# SCH_PDWD-MINI_R2_2022-02-19.net
KiCad netlist of a schematic drawn in EasyEDA
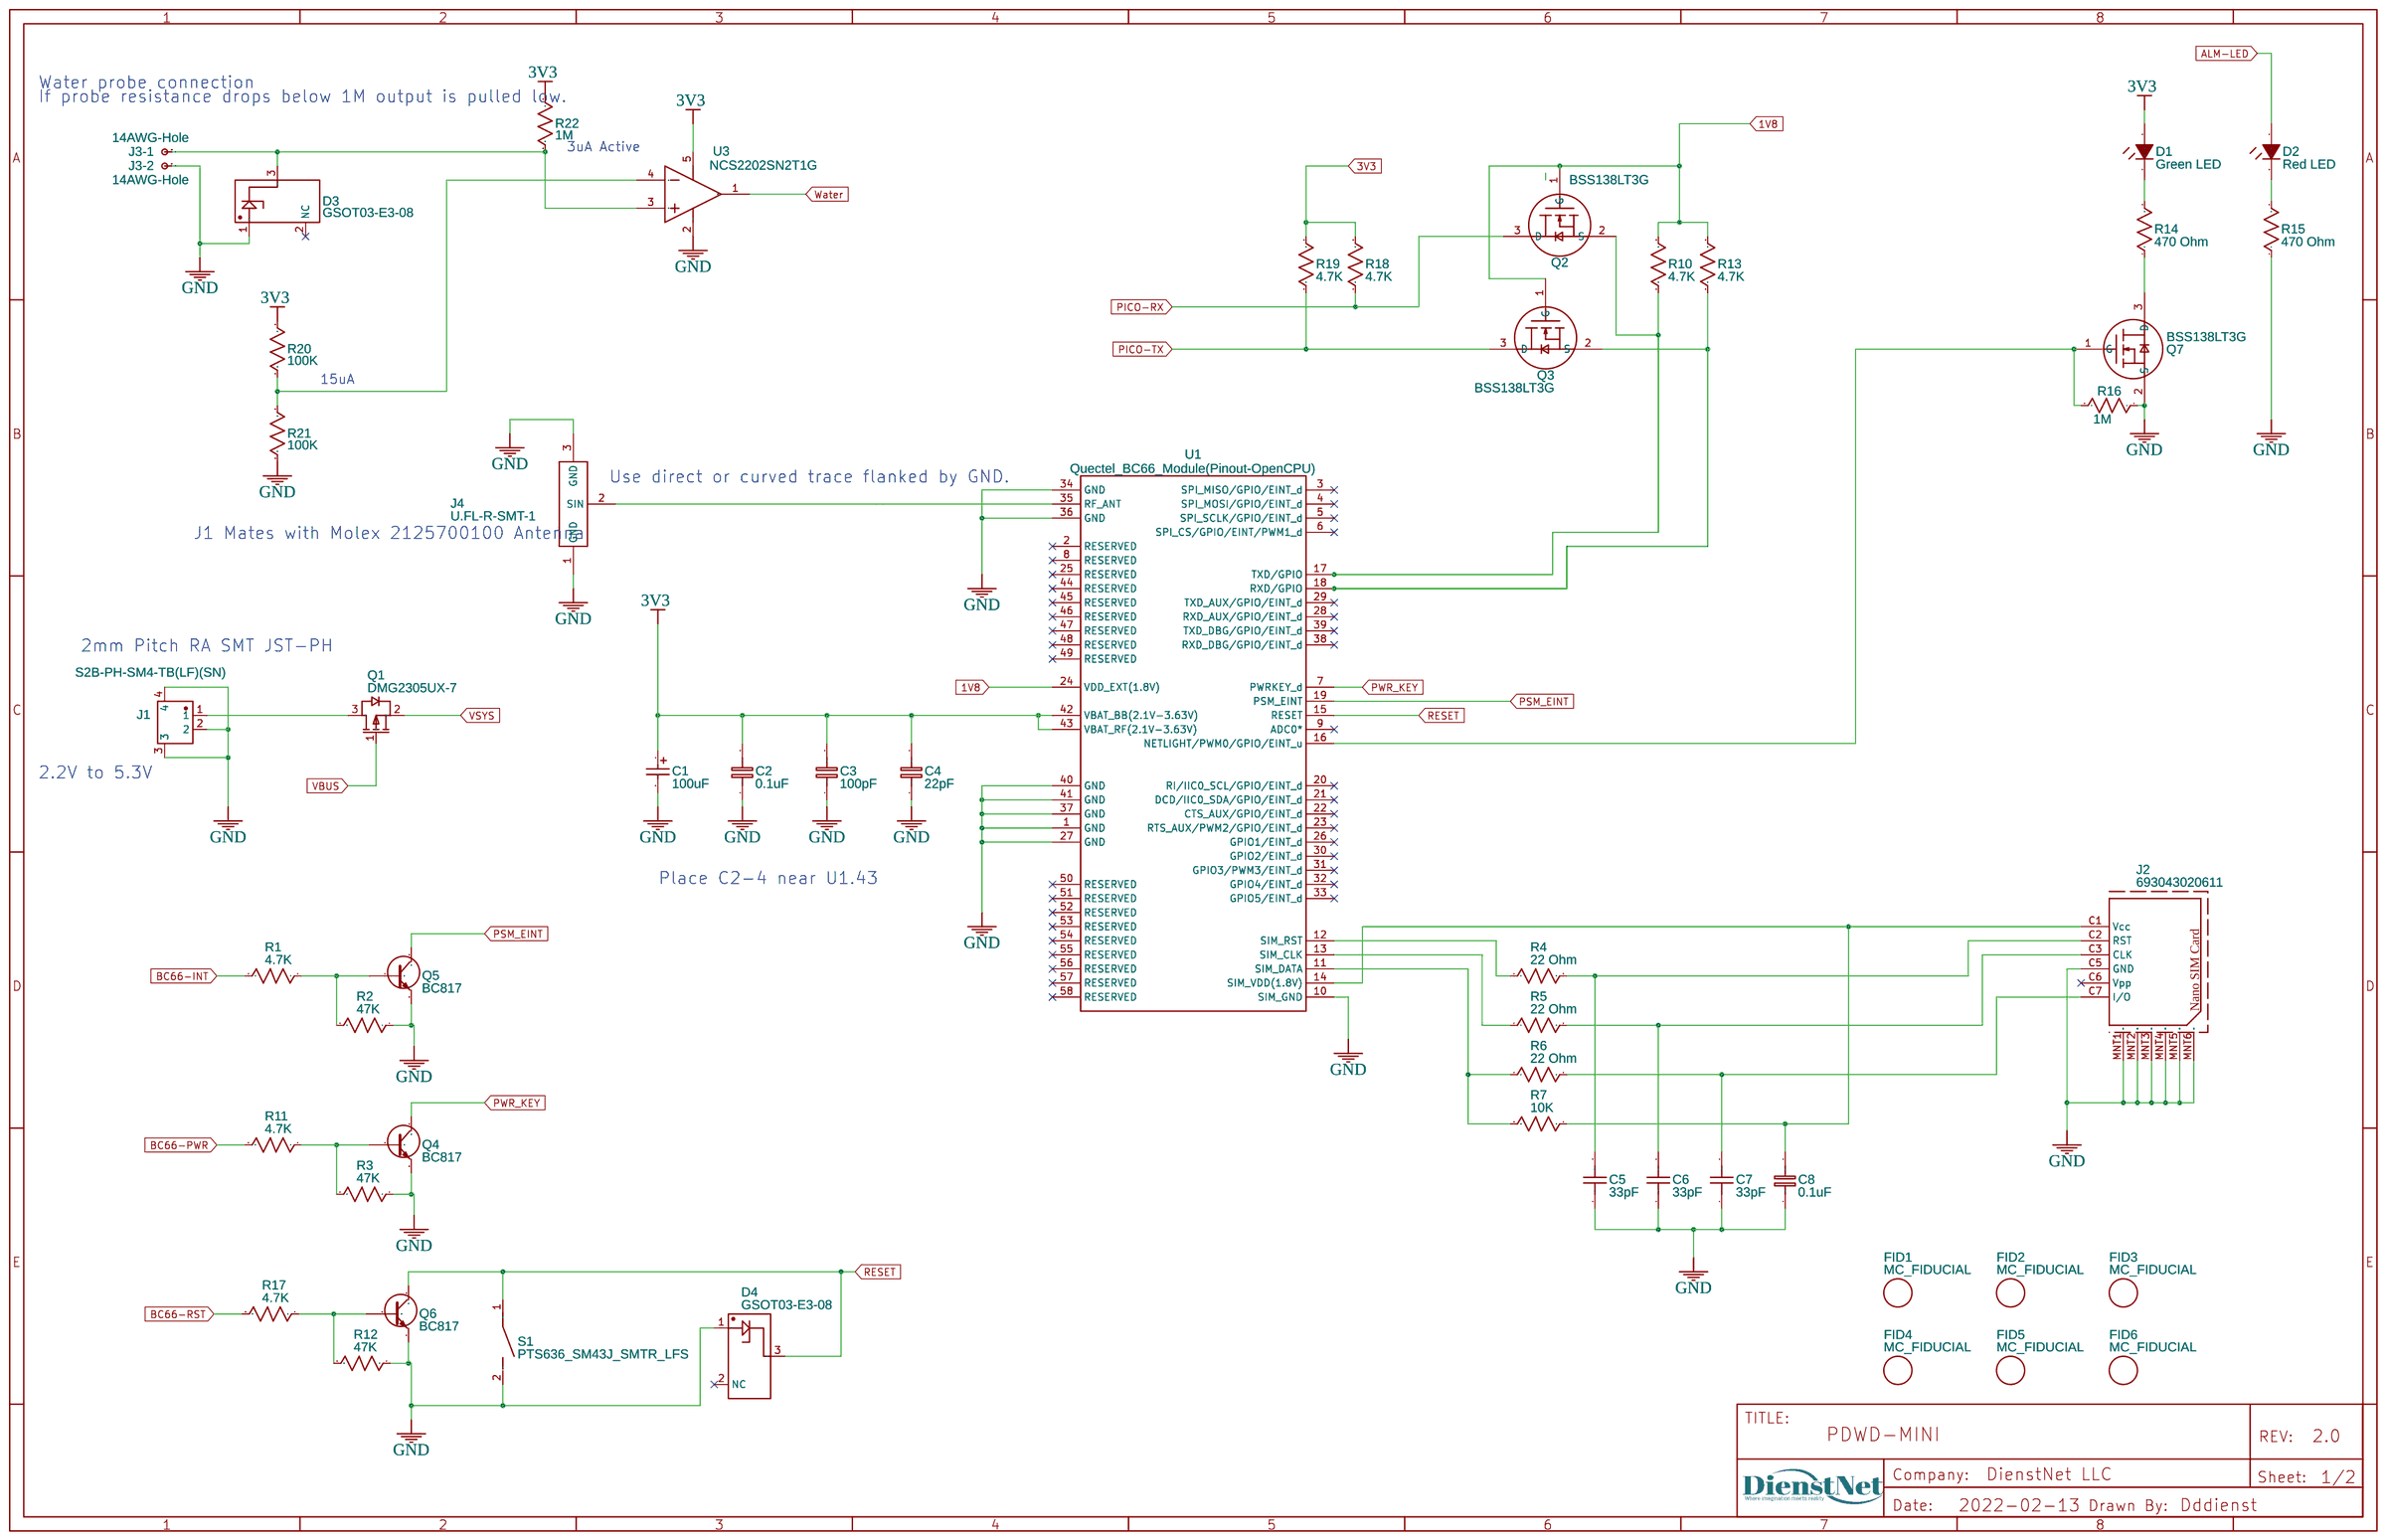
[diagram p0: PDWD-MINI-SCH_Sheet1_R2]
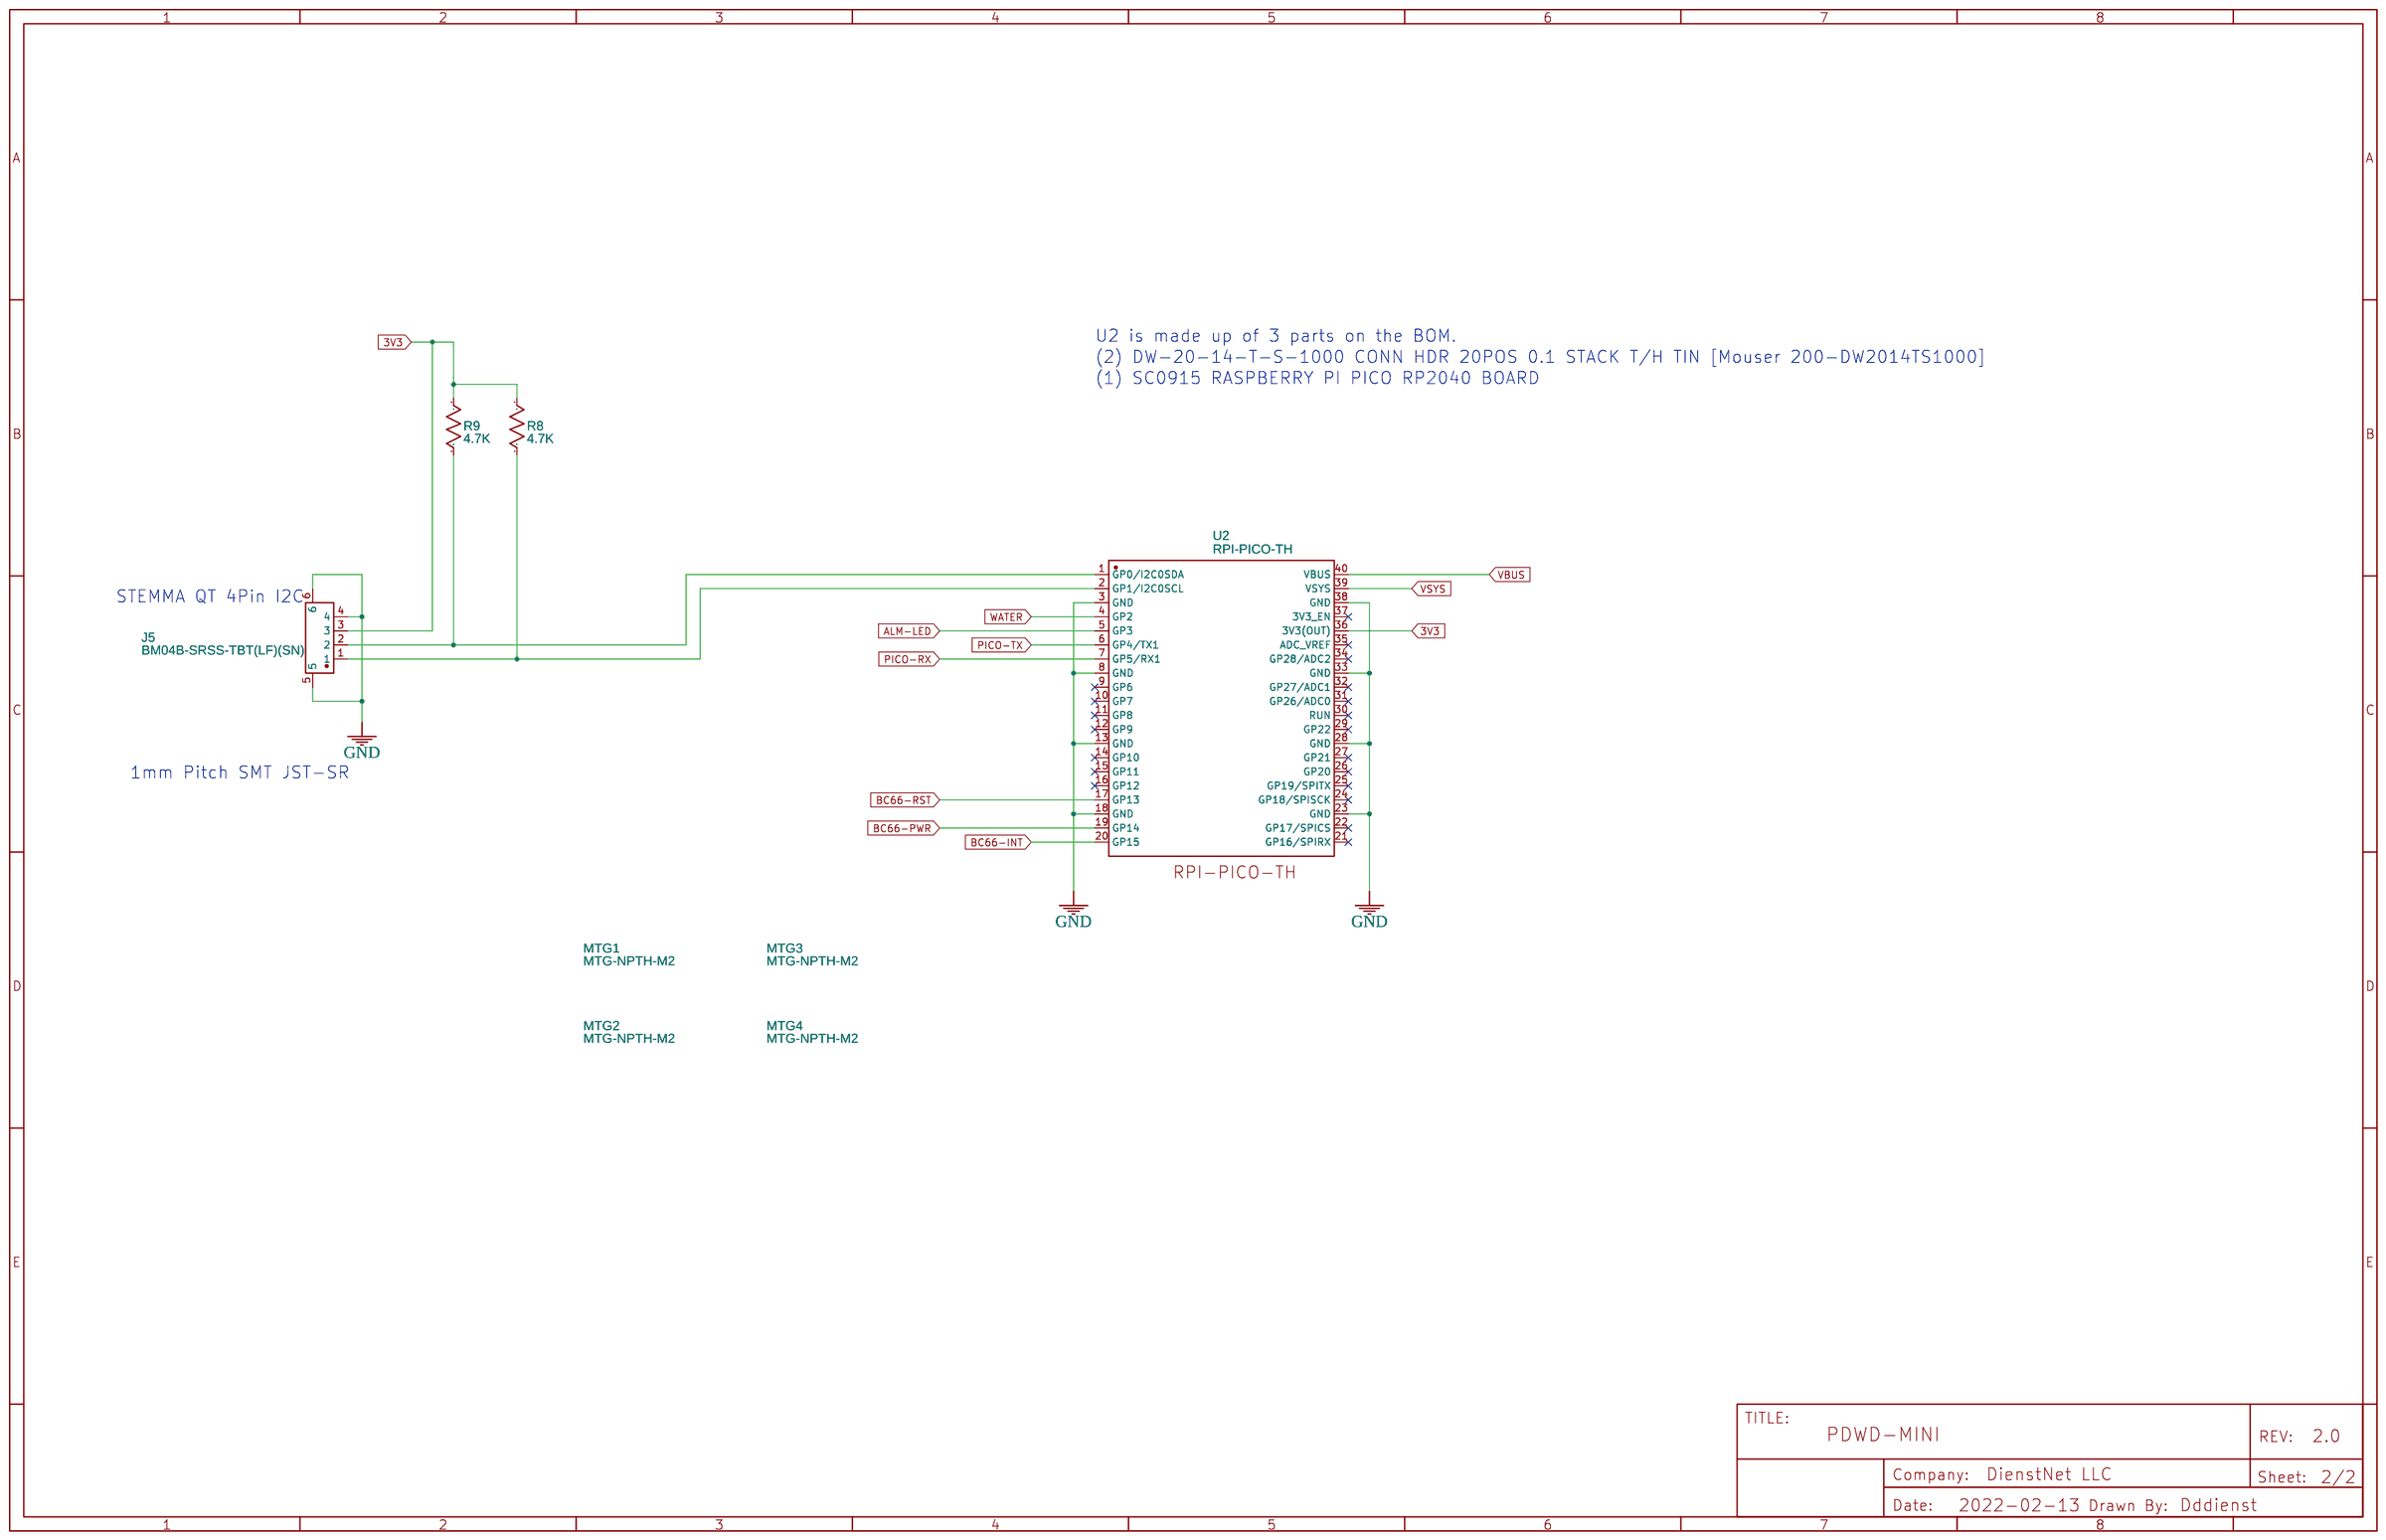
[diagram p1: PICO_Sheet_2_R2]

(export (version "E")
  (design (tool "Eeschema 10.0.6"))
  (components
    (comp (ref "C1")
      (value "100uF")
      (fields
        (field (name "BOM_Manufacturer Part") "TLJA107M006R0500")
        (field (name "BOM_Supplier Part") "C27279")
      )
      (libsource (lib "") (part "TLJA107M006R0800"))
    )
    (comp (ref "C2")
      (value "0.1uF")
      (fields
        (field (name "BOM_Manufacturer Part") "06036C104JAT2A")
        (field (name "BOM_Supplier Part") "C1591")
      )
      (libsource (lib "") (part "C_0603_EU"))
    )
    (comp (ref "C3")
      (value "100pF")
      (fields
        (field (name "BOM_Manufacturer Part") "CC0603KRX7R7BB101")
        (field (name "BOM_Supplier Part") "C62768")
      )
      (libsource (lib "") (part "C_0603_EU"))
    )
    (comp (ref "C4")
      (value "22pF")
      (fields
        (field (name "BOM_Manufacturer Part") "CC0603JRX7R9BB104")
        (field (name "BOM_Supplier Part") "C91183")
      )
      (libsource (lib "") (part "C_0603_EU"))
    )
    (comp (ref "C5")
      (value "33pF")
      (fields
        (field (name "BOM_Manufacturer Part") "C0603C330J5GACTU")
        (field (name "BOM_Supplier Part") "C599724")
      )
      (libsource (lib "") (part "C_0805_US"))
    )
    (comp (ref "C6")
      (value "33pF")
      (fields
        (field (name "BOM_Manufacturer Part") "C0603C330J5GACTU")
        (field (name "BOM_Supplier Part") "C599724")
      )
      (libsource (lib "") (part "C_0805_US"))
    )
    (comp (ref "C7")
      (value "33pF")
      (fields
        (field (name "BOM_Manufacturer Part") "C0603C330J5GACTU")
        (field (name "BOM_Supplier Part") "C599724")
      )
      (libsource (lib "") (part "C_0805_US"))
    )
    (comp (ref "C8")
      (value "0.1uF")
      (fields
        (field (name "BOM_Manufacturer Part") "06036C104JAT2A")
        (field (name "BOM_Supplier Part") "C1591")
      )
      (libsource (lib "") (part "C_0603_EU"))
    )
    (comp (ref "D1")
      (value "Green LED")
      (fields
        (field (name "BOM_Manufacturer Part") "SM0805GCL")
        (field (name "BOM_Supplier Part") "749-SM0805GCL")
      )
      (libsource (lib "") (part "Red LED - SMD"))
    )
    (comp (ref "D2")
      (value "Red LED")
      (fields
        (field (name "BOM_Manufacturer Part") "SM0805HCL")
        (field (name "BOM_Supplier Part") "749-SM0805HCL")
      )
      (libsource (lib "") (part "Red LED - SMD"))
    )
    (comp (ref "D3") (value "GSOT03-E3-08") (libsource (lib "") (part "GSOT03-E3-08_1")))
    (comp (ref "D4") (value "GSOT03-E3-08") (libsource (lib "") (part "GSOT03-E3-08")))
    (comp (ref "FID1") (value "MC_FIDUCIAL") (libsource (lib "") (part "MC_FIDUCIAL")))
    (comp (ref "FID2") (value "MC_FIDUCIAL") (libsource (lib "") (part "MC_FIDUCIAL")))
    (comp (ref "FID3") (value "MC_FIDUCIAL") (libsource (lib "") (part "MC_FIDUCIAL")))
    (comp (ref "FID4") (value "MC_FIDUCIAL") (libsource (lib "") (part "MC_FIDUCIAL")))
    (comp (ref "FID5") (value "MC_FIDUCIAL") (libsource (lib "") (part "MC_FIDUCIAL")))
    (comp (ref "FID6") (value "MC_FIDUCIAL") (libsource (lib "") (part "MC_FIDUCIAL")))
    (comp (ref "J1")
      (value "S2B-PH-SM4-TB(LF)(SN)")
      (fields (field (name "BOM_Supplier Part") "C295747"))
      (libsource (lib "") (part "S2B-PH-SM4-TB(LF)(SN)"))
    )
    (comp (ref "J2")
      (value "693043020611")
      (fields (field (name "BOM_Supplier Part") "732-5954-1-ND"))
      (libsource (lib "") (part "693043020611"))
    )
    (comp (ref "J3-1") (value "14AWG-Hole") (libsource (lib "") (part "14AWG-Hole")))
    (comp (ref "J3-2") (value "14AWG-Hole") (libsource (lib "") (part "14AWG-Hole")))
    (comp (ref "J4")
      (value "U.FL-R-SMT-1")
      (fields
        (field (name "BOM_Manufacturer Part") "U.FL-R-SMT-1(80)")
        (field (name "BOM_Supplier Part") "C88374")
      )
      (libsource (lib "") (part "U.FL-R-SMT-1(80)"))
    )
    (comp (ref "Q1")
      (value "DMG2305UX-7")
      (fields (field (name "BOM_Supplier Part") "C150470"))
      (libsource (lib "") (part "DMG2305UX-7"))
    )
    (comp (ref "Q2")
      (value "BSS138LT3G")
      (fields (field (name "BOM_Supplier Part") "C83790"))
      (libsource (lib "") (part "BSS138LT3G"))
    )
    (comp (ref "Q3")
      (value "BSS138LT3G")
      (fields (field (name "BOM_Supplier Part") "C83790"))
      (libsource (lib "") (part "BSS138LT3G"))
    )
    (comp (ref "Q4")
      (value "BC817")
      (fields
        (field (name "BOM_Manufacturer Part") "BC817-16LT1G")
        (field (name "BOM_Supplier Part") "C94373")
      )
      (libsource (lib "") (part "BC817_1"))
    )
    (comp (ref "Q5")
      (value "BC817")
      (fields
        (field (name "BOM_Manufacturer Part") "BC817-16LT1G")
        (field (name "BOM_Supplier Part") "C94373")
      )
      (libsource (lib "") (part "BC817_2"))
    )
    (comp (ref "Q6")
      (value "BC817")
      (fields
        (field (name "BOM_Manufacturer Part") "BC817-16LT1G")
        (field (name "BOM_Supplier Part") "C94373")
      )
      (libsource (lib "") (part "BC817"))
    )
    (comp (ref "Q7")
      (value "BSS138LT3G")
      (fields (field (name "BOM_Supplier Part") "C83790"))
      (libsource (lib "") (part "BSS138LT3G_1"))
    )
    (comp (ref "R1")
      (value "4.7K")
      (fields
        (field (name "BOM_Manufacturer Part") "ERJ-3GEYJ472V")
        (field (name "BOM_Supplier Part") "C278641")
      )
      (libsource (lib "") (part "R_0805_US"))
    )
    (comp (ref "R2")
      (value "47K")
      (fields
        (field (name "BOM_Manufacturer Part") "ERJ-3GEYJ473V")
        (field (name "BOM_Supplier Part") "C427281")
      )
      (libsource (lib "") (part "R_0805_US"))
    )
    (comp (ref "R3")
      (value "47K")
      (fields
        (field (name "BOM_Manufacturer Part") "ERJ-3GEYJ473V")
        (field (name "BOM_Supplier Part") "C427281")
      )
      (libsource (lib "") (part "R_0805_US"))
    )
    (comp (ref "R4")
      (value "22 Ohm")
      (fields
        (field (name "BOM_Manufacturer Part") "ERJ-3GEYJ220V")
        (field (name "BOM_Supplier Part") "C278638")
      )
      (libsource (lib "") (part "R_0805_US_2"))
    )
    (comp (ref "R5")
      (value "22 Ohm")
      (fields
        (field (name "BOM_Manufacturer Part") "ERJ-3GEYJ220V")
        (field (name "BOM_Supplier Part") "C278638")
      )
      (libsource (lib "") (part "R_0805_US_2"))
    )
    (comp (ref "R6")
      (value "22 Ohm")
      (fields
        (field (name "BOM_Manufacturer Part") "ERJ-3GEYJ220V")
        (field (name "BOM_Supplier Part") "C278638")
      )
      (libsource (lib "") (part "R_0805_US_2"))
    )
    (comp (ref "R7")
      (value "10K")
      (fields
        (field (name "BOM_Manufacturer Part") "ERJ-3GEYJ103V")
        (field (name "BOM_Supplier Part") "C169849")
      )
      (libsource (lib "") (part "R_0805_US"))
    )
    (comp (ref "R10")
      (value "4.7K")
      (fields
        (field (name "BOM_Manufacturer Part") "ERJ-3GEYJ472V")
        (field (name "BOM_Supplier Part") "C278641")
      )
      (libsource (lib "") (part "R_0805_US_1"))
    )
    (comp (ref "R11")
      (value "4.7K")
      (fields
        (field (name "BOM_Manufacturer Part") "ERJ-3GEYJ472V")
        (field (name "BOM_Supplier Part") "C278641")
      )
      (libsource (lib "") (part "R_0805_US"))
    )
    (comp (ref "R12")
      (value "47K")
      (fields
        (field (name "BOM_Manufacturer Part") "ERJ-3GEYJ473V")
        (field (name "BOM_Supplier Part") "C427281")
      )
      (libsource (lib "") (part "R_0805_US"))
    )
    (comp (ref "R13")
      (value "4.7K")
      (fields
        (field (name "BOM_Manufacturer Part") "ERJ-3GEYJ472V")
        (field (name "BOM_Supplier Part") "C278641")
      )
      (libsource (lib "") (part "R_0805_US_1"))
    )
    (comp (ref "R14")
      (value "470 Ohm")
      (fields
        (field (name "BOM_Manufacturer Part") "ERJ-3GEYJ471V")
        (field (name "BOM_Supplier Part") "C169852")
      )
      (libsource (lib "") (part "R_0805_US_1"))
    )
    (comp (ref "R15")
      (value "470 Ohm")
      (fields
        (field (name "BOM_Manufacturer Part") "ERJ-3GEYJ471V")
        (field (name "BOM_Supplier Part") "C169852")
      )
      (libsource (lib "") (part "R_0805_US_1"))
    )
    (comp (ref "R16")
      (value "1M")
      (fields
        (field (name "BOM_Manufacturer Part") "ERJ-3GEYJ105V")
        (field (name "BOM_Supplier Part") "C278634")
      )
      (libsource (lib "") (part "R_0805_US"))
    )
    (comp (ref "R17")
      (value "4.7K")
      (fields
        (field (name "BOM_Manufacturer Part") "ERJ-3GEYJ472V")
        (field (name "BOM_Supplier Part") "C278641")
      )
      (libsource (lib "") (part "R_0805_US"))
    )
    (comp (ref "R18")
      (value "4.7K")
      (fields
        (field (name "BOM_Manufacturer Part") "ERJ-3GEYJ472V")
        (field (name "BOM_Supplier Part") "C278641")
      )
      (libsource (lib "") (part "R_0805_US_1"))
    )
    (comp (ref "R19")
      (value "4.7K")
      (fields
        (field (name "BOM_Manufacturer Part") "ERJ-3GEYJ472V")
        (field (name "BOM_Supplier Part") "C278641")
      )
      (libsource (lib "") (part "R_0805_US_1"))
    )
    (comp (ref "R20")
      (value "100K")
      (fields
        (field (name "BOM_Manufacturer Part") "ERJ-3GEYJ104V")
        (field (name "BOM_Supplier Part") "C427284")
      )
      (libsource (lib "") (part "R_0805_US_3"))
    )
    (comp (ref "R21")
      (value "100K")
      (fields
        (field (name "BOM_Manufacturer Part") "ERJ-3GEYJ104V")
        (field (name "BOM_Supplier Part") "C427284")
      )
      (libsource (lib "") (part "R_0805_US_3"))
    )
    (comp (ref "R22")
      (value "1M")
      (fields
        (field (name "BOM_Manufacturer Part") "ERJ-3GEYJ105V")
        (field (name "BOM_Supplier Part") "C278634")
      )
      (libsource (lib "") (part "R_0805_US_3"))
    )
    (comp (ref "S1")
      (value "PTS636_SM43J_SMTR_LFS")
      (fields
        (field (name "BOM_Manufacturer Part") "PTS636 SM43J SMTR LFS")
        (field (name "BOM_Supplier Part") "611-PTS636SM43JSMTRL")
      )
      (libsource (lib "") (part "PTS636_SM43J_SMTR_LFS"))
    )
    (comp (ref "U1")
      (value "Quectel_BC66_Module(Pinout-OpenCPU)")
      (fields
        (field (name "BOM_Manufacturer Part") "BC66NB-04-STD")
        (field (name "BOM_Supplier Part") "277-BC66NB-04-STD")
      )
      (libsource (lib "") (part "Quectel_BC66_Module(Pinout-OpenCPU)"))
    )
    (comp (ref "U3")
      (value "NCS2202SN2T1G")
      (fields (field (name "BOM_Supplier Part") "C94396"))
      (libsource (lib "") (part "NCS2202SN2T1G"))
    )
    (comp (ref "J5")
      (value "BM04B-SRSS-TBT(LF)(SN)")
      (fields (field (name "BOM_Supplier Part") "C495539"))
      (libsource (lib "") (part "BM04B-SRSS-TBT(LF)(SN)"))
    )
    (comp (ref "MTG1") (value "MTG-NPTH-M2") (libsource (lib "") (part "MTG-NPTH-M2")))
    (comp (ref "MTG2") (value "MTG-NPTH-M2") (libsource (lib "") (part "MTG-NPTH-M2")))
    (comp (ref "MTG3") (value "MTG-NPTH-M2") (libsource (lib "") (part "MTG-NPTH-M2")))
    (comp (ref "MTG4") (value "MTG-NPTH-M2") (libsource (lib "") (part "MTG-NPTH-M2")))
    (comp (ref "R8")
      (value "4.7K")
      (fields
        (field (name "BOM_Manufacturer Part") "ERJ-3GEYJ472V")
        (field (name "BOM_Supplier Part") "C278641")
      )
      (libsource (lib "") (part "R_0805_US"))
    )
    (comp (ref "R9")
      (value "4.7K")
      (fields
        (field (name "BOM_Manufacturer Part") "ERJ-3GEYJ472V")
        (field (name "BOM_Supplier Part") "C278641")
      )
      (libsource (lib "") (part "R_0805_US"))
    )
    (comp (ref "U2")
      (value "RPI-PICO-TH")
      (fields
        (field (name "BOM_Manufacturer Part") "SC0915")
        (field (name "BOM_Supplier Part") "2648-SC0915CT-ND")
      )
      (libsource (lib "") (part "RPI-PICO-TH"))
    )
  )
  (nets
    (net (code "1") (name "1V8") (class "Default")
      (node (ref "Q2") (pin "1") (pinfunction "G_1") (pintype "unspecified"))
      (node (ref "Q3") (pin "1") (pinfunction "G_1") (pintype "unspecified"))
      (node (ref "R10") (pin "2") (pinfunction "2_2") (pintype "unspecified"))
      (node (ref "R13") (pin "2") (pinfunction "2_2") (pintype "unspecified"))
      (node (ref "U1") (pin "24") (pinfunction "VDD_EXT(1.8V)_24") (pintype "unspecified"))
    )
    (net (code "2") (name "3V3") (class "Default")
      (node (ref "C1") (pin "1") (pinfunction "1_1") (pintype "input"))
      (node (ref "C2") (pin "2") (pinfunction "2_2") (pintype "unspecified"))
      (node (ref "C3") (pin "2") (pinfunction "2_2") (pintype "unspecified"))
      (node (ref "C4") (pin "2") (pinfunction "2_2") (pintype "unspecified"))
      (node (ref "D1") (pin "1") (pinfunction "A_1") (pintype "unspecified"))
      (node (ref "J5") (pin "3") (pinfunction "3_3") (pintype "unspecified"))
      (node (ref "R18") (pin "2") (pinfunction "2_2") (pintype "unspecified"))
      (node (ref "R19") (pin "2") (pinfunction "2_2") (pintype "unspecified"))
      (node (ref "R20") (pin "1") (pinfunction "1_1") (pintype "unspecified"))
      (node (ref "R22") (pin "1") (pinfunction "1_1") (pintype "unspecified"))
      (node (ref "R8") (pin "2") (pinfunction "2_2") (pintype "unspecified"))
      (node (ref "R9") (pin "2") (pinfunction "2_2") (pintype "unspecified"))
      (node (ref "U1") (pin "42") (pinfunction "VBAT_BB(2.1V-3.63V)_42") (pintype "unspecified"))
      (node (ref "U1") (pin "43") (pinfunction "VBAT_RF(2.1V-3.63V)_43") (pintype "unspecified"))
      (node (ref "U2") (pin "36") (pinfunction "3V3(OUT)_36") (pintype "unspecified"))
      (node (ref "U3") (pin "5") (pinfunction "+V_5") (pintype "passive"))
    )
    (net (code "3") (name "ALM-LED") (class "Default")
      (node (ref "D2") (pin "1") (pinfunction "A_1") (pintype "unspecified"))
      (node (ref "U2") (pin "5") (pinfunction "GP3_5") (pintype "unspecified"))
    )
    (net (code "4") (name "BC66-INT") (class "Default")
      (node (ref "R1") (pin "2") (pinfunction "2_2") (pintype "unspecified"))
      (node (ref "U2") (pin "20") (pinfunction "GP15_20") (pintype "unspecified"))
    )
    (net (code "5") (name "BC66-PWR") (class "Default")
      (node (ref "R11") (pin "2") (pinfunction "2_2") (pintype "unspecified"))
      (node (ref "U2") (pin "19") (pinfunction "GP14_19") (pintype "unspecified"))
    )
    (net (code "6") (name "BC66-RST") (class "Default")
      (node (ref "R17") (pin "2") (pinfunction "2_2") (pintype "unspecified"))
      (node (ref "U2") (pin "17") (pinfunction "GP13_17") (pintype "unspecified"))
    )
    (net (code "7") (name "GND") (class "Default")
      (node (ref "C1") (pin "2") (pinfunction "2_2") (pintype "input"))
      (node (ref "C2") (pin "1") (pinfunction "1_1") (pintype "unspecified"))
      (node (ref "C3") (pin "1") (pinfunction "1_1") (pintype "unspecified"))
      (node (ref "C4") (pin "1") (pinfunction "1_1") (pintype "unspecified"))
      (node (ref "C5") (pin "1") (pinfunction "1_1") (pintype "unspecified"))
      (node (ref "C6") (pin "1") (pinfunction "1_1") (pintype "unspecified"))
      (node (ref "C7") (pin "1") (pinfunction "1_1") (pintype "unspecified"))
      (node (ref "C8") (pin "1") (pinfunction "1_1") (pintype "unspecified"))
      (node (ref "D3") (pin "1") (pinfunction "IN_1") (pintype "unspecified"))
      (node (ref "D4") (pin "1") (pinfunction "IN_1") (pintype "unspecified"))
      (node (ref "J1") (pin "2") (pinfunction "2_2") (pintype "unspecified"))
      (node (ref "J1") (pin "3") (pinfunction "3_3") (pintype "unspecified"))
      (node (ref "J1") (pin "4") (pinfunction "4_4") (pintype "unspecified"))
      (node (ref "J2") (pin "C5") (pinfunction "GND_C5") (pintype "unspecified"))
      (node (ref "J2") (pin "MNT1") (pinfunction "Shield_MNT1") (pintype "unspecified"))
      (node (ref "J2") (pin "MNT2") (pinfunction "Shield_MNT2") (pintype "unspecified"))
      (node (ref "J2") (pin "MNT3") (pinfunction "Shield_MNT3") (pintype "unspecified"))
      (node (ref "J2") (pin "MNT4") (pinfunction "Shield_MNT4") (pintype "unspecified"))
      (node (ref "J2") (pin "MNT5") (pinfunction "Shield_MNT5") (pintype "unspecified"))
      (node (ref "J2") (pin "MNT6") (pinfunction "Shield_MNT6") (pintype "unspecified"))
      (node (ref "J3-2") (pin "P$1") (pinfunction "P$1_P$1") (pintype "unspecified"))
      (node (ref "J4") (pin "1") (pinfunction "GND_1") (pintype "unspecified"))
      (node (ref "J4") (pin "3") (pinfunction "GND_3") (pintype "unspecified"))
      (node (ref "J5") (pin "4") (pinfunction "4_4") (pintype "unspecified"))
      (node (ref "J5") (pin "5") (pinfunction "5_5") (pintype "unspecified"))
      (node (ref "J5") (pin "6") (pinfunction "6_6") (pintype "unspecified"))
      (node (ref "Q4") (pin "2") (pinfunction "E_2") (pintype "unspecified"))
      (node (ref "Q5") (pin "2") (pinfunction "E_2") (pintype "unspecified"))
      (node (ref "Q6") (pin "2") (pinfunction "E_2") (pintype "unspecified"))
      (node (ref "Q7") (pin "2") (pinfunction "S_2") (pintype "unspecified"))
      (node (ref "R12") (pin "1") (pinfunction "1_1") (pintype "unspecified"))
      (node (ref "R15") (pin "1") (pinfunction "1_1") (pintype "unspecified"))
      (node (ref "R16") (pin "1") (pinfunction "1_1") (pintype "unspecified"))
      (node (ref "R2") (pin "1") (pinfunction "1_1") (pintype "unspecified"))
      (node (ref "R21") (pin "2") (pinfunction "2_2") (pintype "unspecified"))
      (node (ref "R3") (pin "1") (pinfunction "1_1") (pintype "unspecified"))
      (node (ref "S1") (pin "2") (pinfunction "NO_2") (pintype "bidirectional"))
      (node (ref "U1") (pin "1") (pinfunction "GND_1") (pintype "unspecified"))
      (node (ref "U1") (pin "10") (pinfunction "SIM_GND_10") (pintype "unspecified"))
      (node (ref "U1") (pin "27") (pinfunction "GND_27") (pintype "unspecified"))
      (node (ref "U1") (pin "34") (pinfunction "GND_34") (pintype "unspecified"))
      (node (ref "U1") (pin "36") (pinfunction "GND_36") (pintype "unspecified"))
      (node (ref "U1") (pin "37") (pinfunction "GND_37") (pintype "unspecified"))
      (node (ref "U1") (pin "40") (pinfunction "GND_40") (pintype "unspecified"))
      (node (ref "U1") (pin "41") (pinfunction "GND_41") (pintype "unspecified"))
      (node (ref "U2") (pin "13") (pinfunction "GND_13") (pintype "unspecified"))
      (node (ref "U2") (pin "18") (pinfunction "GND_18") (pintype "unspecified"))
      (node (ref "U2") (pin "23") (pinfunction "GND_23") (pintype "unspecified"))
      (node (ref "U2") (pin "28") (pinfunction "GND_28") (pintype "unspecified"))
      (node (ref "U2") (pin "3") (pinfunction "GND_3") (pintype "unspecified"))
      (node (ref "U2") (pin "33") (pinfunction "GND_33") (pintype "unspecified"))
      (node (ref "U2") (pin "38") (pinfunction "GND_38") (pintype "unspecified"))
      (node (ref "U2") (pin "8") (pinfunction "GND_8") (pintype "unspecified"))
      (node (ref "U3") (pin "2") (pinfunction "-V_2") (pintype "passive"))
    )
    (net (code "8") (name "Net-(D1-K)") (class "Default")
      (node (ref "D1") (pin "2") (pinfunction "K_2") (pintype "unspecified"))
      (node (ref "R14") (pin "2") (pinfunction "2_2") (pintype "unspecified"))
    )
    (net (code "9") (name "Net-(D2-K)") (class "Default")
      (node (ref "D2") (pin "2") (pinfunction "K_2") (pintype "unspecified"))
      (node (ref "R15") (pin "2") (pinfunction "2_2") (pintype "unspecified"))
    )
    (net (code "10") (name "Net-(D3-OUT)") (class "Default")
      (node (ref "D3") (pin "3") (pinfunction "OUT_3") (pintype "unspecified"))
      (node (ref "J3-1") (pin "P$1") (pinfunction "P$1_P$1") (pintype "unspecified"))
      (node (ref "R22") (pin "2") (pinfunction "2_2") (pintype "unspecified"))
      (node (ref "U3") (pin "3") (pinfunction "+IN_3") (pintype "unspecified"))
    )
    (net (code "11") (name "Net-(J2-CLK)") (class "Default")
      (node (ref "C6") (pin "2") (pinfunction "2_2") (pintype "unspecified"))
      (node (ref "J2") (pin "C3") (pinfunction "CLK_C3") (pintype "unspecified"))
      (node (ref "R5") (pin "2") (pinfunction "2_2") (pintype "unspecified"))
    )
    (net (code "12") (name "Net-(J2-I{slash}O)") (class "Default")
      (node (ref "C7") (pin "2") (pinfunction "2_2") (pintype "unspecified"))
      (node (ref "J2") (pin "C7") (pinfunction "I/O_C7") (pintype "unspecified"))
      (node (ref "R6") (pin "2") (pinfunction "2_2") (pintype "unspecified"))
    )
    (net (code "13") (name "Net-(J2-RST)") (class "Default")
      (node (ref "C5") (pin "2") (pinfunction "2_2") (pintype "unspecified"))
      (node (ref "J2") (pin "C2") (pinfunction "RST_C2") (pintype "unspecified"))
      (node (ref "R4") (pin "2") (pinfunction "2_2") (pintype "unspecified"))
    )
    (net (code "14") (name "Net-(J2-Vcc)") (class "Default")
      (node (ref "C8") (pin "2") (pinfunction "2_2") (pintype "unspecified"))
      (node (ref "J2") (pin "C1") (pinfunction "Vcc_C1") (pintype "unspecified"))
      (node (ref "R7") (pin "1") (pinfunction "1_1") (pintype "unspecified"))
      (node (ref "U1") (pin "14") (pinfunction "SIM_VDD(1.8V)_14") (pintype "unspecified"))
    )
    (net (code "15") (name "Net-(J4-SIN)") (class "Default")
      (node (ref "J4") (pin "2") (pinfunction "SIN_2") (pintype "unspecified"))
      (node (ref "U1") (pin "35") (pinfunction "RF_ANT_35") (pintype "unspecified"))
    )
    (net (code "16") (name "Net-(Q1-D)") (class "Default")
      (node (ref "J1") (pin "1") (pinfunction "1_1") (pintype "unspecified"))
      (node (ref "Q1") (pin "3") (pinfunction "D_3") (pintype "unspecified"))
    )
    (net (code "17") (name "Net-(Q2-S)") (class "Default")
      (node (ref "Q2") (pin "2") (pinfunction "S_2") (pintype "unspecified"))
      (node (ref "R10") (pin "1") (pinfunction "1_1") (pintype "unspecified"))
      (node (ref "U1") (pin "17") (pinfunction "TXD/GPIO_17") (pintype "unspecified"))
    )
    (net (code "18") (name "Net-(Q3-S)") (class "Default")
      (node (ref "Q3") (pin "2") (pinfunction "S_2") (pintype "unspecified"))
      (node (ref "R13") (pin "1") (pinfunction "1_1") (pintype "unspecified"))
      (node (ref "U1") (pin "18") (pinfunction "RXD/GPIO_18") (pintype "unspecified"))
    )
    (net (code "19") (name "Net-(Q4-B)") (class "Default")
      (node (ref "Q4") (pin "1") (pinfunction "B_1") (pintype "input"))
      (node (ref "R11") (pin "1") (pinfunction "1_1") (pintype "unspecified"))
      (node (ref "R3") (pin "2") (pinfunction "2_2") (pintype "unspecified"))
    )
    (net (code "20") (name "Net-(Q5-B)") (class "Default")
      (node (ref "Q5") (pin "1") (pinfunction "B_1") (pintype "input"))
      (node (ref "R1") (pin "1") (pinfunction "1_1") (pintype "unspecified"))
      (node (ref "R2") (pin "2") (pinfunction "2_2") (pintype "unspecified"))
    )
    (net (code "21") (name "Net-(Q6-B)") (class "Default")
      (node (ref "Q6") (pin "1") (pinfunction "B_1") (pintype "input"))
      (node (ref "R12") (pin "2") (pinfunction "2_2") (pintype "unspecified"))
      (node (ref "R17") (pin "1") (pinfunction "1_1") (pintype "unspecified"))
    )
    (net (code "22") (name "Net-(Q7-D)") (class "Default")
      (node (ref "Q7") (pin "3") (pinfunction "D_3") (pintype "unspecified"))
      (node (ref "R14") (pin "1") (pinfunction "1_1") (pintype "unspecified"))
    )
    (net (code "23") (name "Net-(Q7-G)") (class "Default")
      (node (ref "Q7") (pin "1") (pinfunction "G_1") (pintype "unspecified"))
      (node (ref "R16") (pin "2") (pinfunction "2_2") (pintype "unspecified"))
      (node (ref "U1") (pin "16") (pinfunction "NETLIGHT/PWM0/GPIO/EINT_u_16") (pintype "unspecified"))
    )
    (net (code "24") (name "Net-(U1-SIM_CLK)") (class "Default")
      (node (ref "R5") (pin "1") (pinfunction "1_1") (pintype "unspecified"))
      (node (ref "U1") (pin "13") (pinfunction "SIM_CLK_13") (pintype "unspecified"))
    )
    (net (code "25") (name "Net-(U1-SIM_DATA)") (class "Default")
      (node (ref "R6") (pin "1") (pinfunction "1_1") (pintype "unspecified"))
      (node (ref "R7") (pin "2") (pinfunction "2_2") (pintype "unspecified"))
      (node (ref "U1") (pin "11") (pinfunction "SIM_DATA_11") (pintype "unspecified"))
    )
    (net (code "26") (name "Net-(U1-SIM_RST)") (class "Default")
      (node (ref "R4") (pin "1") (pinfunction "1_1") (pintype "unspecified"))
      (node (ref "U1") (pin "12") (pinfunction "SIM_RST_12") (pintype "unspecified"))
    )
    (net (code "27") (name "Net-(U2-GP0{slash}I2C0SDA)") (class "Default")
      (node (ref "J5") (pin "2") (pinfunction "2_2") (pintype "unspecified"))
      (node (ref "R9") (pin "1") (pinfunction "1_1") (pintype "unspecified"))
      (node (ref "U2") (pin "1") (pinfunction "GP0/I2C0SDA_1") (pintype "unspecified"))
    )
    (net (code "28") (name "Net-(U2-GP1{slash}I2C0SCL)") (class "Default")
      (node (ref "J5") (pin "1") (pinfunction "1_1") (pintype "unspecified"))
      (node (ref "R8") (pin "1") (pinfunction "1_1") (pintype "unspecified"))
      (node (ref "U2") (pin "2") (pinfunction "GP1/I2C0SCL_2") (pintype "unspecified"))
    )
    (net (code "29") (name "Net-(U3--IN)") (class "Default")
      (node (ref "R20") (pin "2") (pinfunction "2_2") (pintype "unspecified"))
      (node (ref "R21") (pin "1") (pinfunction "1_1") (pintype "unspecified"))
      (node (ref "U3") (pin "4") (pinfunction "-IN_4") (pintype "unspecified"))
    )
    (net (code "30") (name "PICO-RX") (class "Default")
      (node (ref "Q2") (pin "3") (pinfunction "D_3") (pintype "unspecified"))
      (node (ref "R18") (pin "1") (pinfunction "1_1") (pintype "unspecified"))
      (node (ref "U2") (pin "7") (pinfunction "GP5/RX1_7") (pintype "unspecified"))
    )
    (net (code "31") (name "PICO-TX") (class "Default")
      (node (ref "Q3") (pin "3") (pinfunction "D_3") (pintype "unspecified"))
      (node (ref "R19") (pin "1") (pinfunction "1_1") (pintype "unspecified"))
      (node (ref "U2") (pin "6") (pinfunction "GP4/TX1_6") (pintype "unspecified"))
    )
    (net (code "32") (name "PSM_EINT") (class "Default")
      (node (ref "Q5") (pin "3") (pinfunction "C_3") (pintype "unspecified"))
      (node (ref "U1") (pin "19") (pinfunction "PSM_EINT_19") (pintype "unspecified"))
    )
    (net (code "33") (name "PWR_KEY") (class "Default")
      (node (ref "Q4") (pin "3") (pinfunction "C_3") (pintype "unspecified"))
      (node (ref "U1") (pin "7") (pinfunction "PWRKEY_d_7") (pintype "unspecified"))
    )
    (net (code "34") (name "RESET") (class "Default")
      (node (ref "D4") (pin "3") (pinfunction "OUT_3") (pintype "unspecified"))
      (node (ref "Q6") (pin "3") (pinfunction "C_3") (pintype "unspecified"))
      (node (ref "S1") (pin "1") (pinfunction "COM_1") (pintype "bidirectional"))
      (node (ref "U1") (pin "15") (pinfunction "RESET_15") (pintype "unspecified"))
    )
    (net (code "35") (name "VBUS") (class "Default")
      (node (ref "Q1") (pin "1") (pinfunction "G_1") (pintype "unspecified"))
      (node (ref "U2") (pin "40") (pinfunction "VBUS_40") (pintype "unspecified"))
    )
    (net (code "36") (name "VSYS") (class "Default")
      (node (ref "Q1") (pin "2") (pinfunction "S_2") (pintype "unspecified"))
      (node (ref "U2") (pin "39") (pinfunction "VSYS_39") (pintype "unspecified"))
    )
    (net (code "37") (name "WATER") (class "Default")
      (node (ref "U2") (pin "4") (pinfunction "GP2_4") (pintype "unspecified"))
    )
    (net (code "38") (name "Water") (class "Default")
      (node (ref "U3") (pin "1") (pinfunction "OUT_1") (pintype "output"))
    )
    (net (code "39") (name "unconnected-(D3-NC-Pad2)") (class "Default")
      (node (ref "D3") (pin "2") (pinfunction "NC_2") (pintype "unspecified+no_connect"))
    )
    (net (code "40") (name "unconnected-(D4-NC-Pad2)") (class "Default")
      (node (ref "D4") (pin "2") (pinfunction "NC_2") (pintype "unspecified+no_connect"))
    )
    (net (code "41") (name "unconnected-(J2-Vpp-PadC6)") (class "Default")
      (node (ref "J2") (pin "C6") (pinfunction "Vpp_C6") (pintype "unspecified+no_connect"))
    )
    (net (code "42") (name "unconnected-(U1-ADC0*-Pad9)") (class "Default")
      (node (ref "U1") (pin "9") (pinfunction "ADC0*_9") (pintype "unspecified+no_connect"))
    )
    (net (code "43") (name "unconnected-(U1-CTS_AUX{slash}GPIO{slash}EINT_d-Pad22)") (class "Default")
      (node (ref "U1") (pin "22") (pinfunction "CTS_AUX/GPIO/EINT_d_22") (pintype "unspecified+no_connect"))
    )
    (net (code "44") (name "unconnected-(U1-DCD{slash}IIC0_SDA{slash}GPIO{slash}EINT_d-Pad21)") (class "Default")
      (node (ref "U1") (pin "21") (pinfunction "DCD/IIC0_SDA/GPIO/EINT_d_21") (pintype "unspecified+no_connect"))
    )
    (net (code "45") (name "unconnected-(U1-GPIO1{slash}EINT_d-Pad26)") (class "Default")
      (node (ref "U1") (pin "26") (pinfunction "GPIO1/EINT_d_26") (pintype "unspecified+no_connect"))
    )
    (net (code "46") (name "unconnected-(U1-GPIO2{slash}EINT_d-Pad30)") (class "Default")
      (node (ref "U1") (pin "30") (pinfunction "GPIO2/EINT_d_30") (pintype "unspecified+no_connect"))
    )
    (net (code "47") (name "unconnected-(U1-GPIO3{slash}PWM3{slash}EINT_d-Pad31)") (class "Default")
      (node (ref "U1") (pin "31") (pinfunction "GPIO3/PWM3/EINT_d_31") (pintype "unspecified+no_connect"))
    )
    (net (code "48") (name "unconnected-(U1-GPIO4{slash}EINT_d-Pad32)") (class "Default")
      (node (ref "U1") (pin "32") (pinfunction "GPIO4/EINT_d_32") (pintype "unspecified+no_connect"))
    )
    (net (code "49") (name "unconnected-(U1-GPIO5{slash}EINT_d-Pad33)") (class "Default")
      (node (ref "U1") (pin "33") (pinfunction "GPIO5/EINT_d_33") (pintype "unspecified+no_connect"))
    )
    (net (code "50") (name "unconnected-(U1-RESERVED-Pad2)") (class "Default")
      (node (ref "U1") (pin "2") (pinfunction "RESERVED_2") (pintype "unspecified+no_connect"))
    )
    (net (code "51") (name "unconnected-(U1-RESERVED-Pad8)") (class "Default")
      (node (ref "U1") (pin "8") (pinfunction "RESERVED_8") (pintype "unspecified+no_connect"))
    )
    (net (code "52") (name "unconnected-(U1-RESERVED-Pad25)") (class "Default")
      (node (ref "U1") (pin "25") (pinfunction "RESERVED_25") (pintype "unspecified+no_connect"))
    )
    (net (code "53") (name "unconnected-(U1-RESERVED-Pad44)") (class "Default")
      (node (ref "U1") (pin "44") (pinfunction "RESERVED_44") (pintype "unspecified+no_connect"))
    )
    (net (code "54") (name "unconnected-(U1-RESERVED-Pad45)") (class "Default")
      (node (ref "U1") (pin "45") (pinfunction "RESERVED_45") (pintype "unspecified+no_connect"))
    )
    (net (code "55") (name "unconnected-(U1-RESERVED-Pad46)") (class "Default")
      (node (ref "U1") (pin "46") (pinfunction "RESERVED_46") (pintype "unspecified+no_connect"))
    )
    (net (code "56") (name "unconnected-(U1-RESERVED-Pad47)") (class "Default")
      (node (ref "U1") (pin "47") (pinfunction "RESERVED_47") (pintype "unspecified+no_connect"))
    )
    (net (code "57") (name "unconnected-(U1-RESERVED-Pad48)") (class "Default")
      (node (ref "U1") (pin "48") (pinfunction "RESERVED_48") (pintype "unspecified+no_connect"))
    )
    (net (code "58") (name "unconnected-(U1-RESERVED-Pad49)") (class "Default")
      (node (ref "U1") (pin "49") (pinfunction "RESERVED_49") (pintype "unspecified+no_connect"))
    )
    (net (code "59") (name "unconnected-(U1-RESERVED-Pad50)") (class "Default")
      (node (ref "U1") (pin "50") (pinfunction "RESERVED_50") (pintype "unspecified+no_connect"))
    )
    (net (code "60") (name "unconnected-(U1-RESERVED-Pad51)") (class "Default")
      (node (ref "U1") (pin "51") (pinfunction "RESERVED_51") (pintype "unspecified+no_connect"))
    )
    (net (code "61") (name "unconnected-(U1-RESERVED-Pad52)") (class "Default")
      (node (ref "U1") (pin "52") (pinfunction "RESERVED_52") (pintype "unspecified+no_connect"))
    )
    (net (code "62") (name "unconnected-(U1-RESERVED-Pad53)") (class "Default")
      (node (ref "U1") (pin "53") (pinfunction "RESERVED_53") (pintype "unspecified+no_connect"))
    )
    (net (code "63") (name "unconnected-(U1-RESERVED-Pad54)") (class "Default")
      (node (ref "U1") (pin "54") (pinfunction "RESERVED_54") (pintype "unspecified+no_connect"))
    )
    (net (code "64") (name "unconnected-(U1-RESERVED-Pad55)") (class "Default")
      (node (ref "U1") (pin "55") (pinfunction "RESERVED_55") (pintype "unspecified+no_connect"))
    )
    (net (code "65") (name "unconnected-(U1-RESERVED-Pad56)") (class "Default")
      (node (ref "U1") (pin "56") (pinfunction "RESERVED_56") (pintype "unspecified+no_connect"))
    )
    (net (code "66") (name "unconnected-(U1-RESERVED-Pad57)") (class "Default")
      (node (ref "U1") (pin "57") (pinfunction "RESERVED_57") (pintype "unspecified+no_connect"))
    )
    (net (code "67") (name "unconnected-(U1-RESERVED-Pad58)") (class "Default")
      (node (ref "U1") (pin "58") (pinfunction "RESERVED_58") (pintype "unspecified+no_connect"))
    )
    (net (code "68") (name "unconnected-(U1-RI{slash}IIC0_SCL{slash}GPIO{slash}EINT_d-Pad20)") (class "Default")
      (node (ref "U1") (pin "20") (pinfunction "RI/IIC0_SCL/GPIO/EINT_d_20") (pintype "unspecified+no_connect"))
    )
    (net (code "69") (name "unconnected-(U1-RTS_AUX{slash}PWM2{slash}GPIO{slash}EINT_d-Pad23)") (class "Default")
      (node (ref "U1") (pin "23") (pinfunction "RTS_AUX/PWM2/GPIO/EINT_d_23") (pintype "unspecified+no_connect"))
    )
    (net (code "70") (name "unconnected-(U1-RXD_AUX{slash}GPIO{slash}EINT_d-Pad28)") (class "Default")
      (node (ref "U1") (pin "28") (pinfunction "RXD_AUX/GPIO/EINT_d_28") (pintype "unspecified+no_connect"))
    )
    (net (code "71") (name "unconnected-(U1-RXD_DBG{slash}GPIO{slash}EINT_d-Pad38)") (class "Default")
      (node (ref "U1") (pin "38") (pinfunction "RXD_DBG/GPIO/EINT_d_38") (pintype "unspecified+no_connect"))
    )
    (net (code "72") (name "unconnected-(U1-SPI_CS{slash}GPIO{slash}EINT{slash}PWM1_d-Pad6)") (class "Default")
      (node (ref "U1") (pin "6") (pinfunction "SPI_CS/GPIO/EINT/PWM1_d_6") (pintype "unspecified+no_connect"))
    )
    (net (code "73") (name "unconnected-(U1-SPI_MISO{slash}GPIO{slash}EINT_d-Pad3)") (class "Default")
      (node (ref "U1") (pin "3") (pinfunction "SPI_MISO/GPIO/EINT_d_3") (pintype "unspecified+no_connect"))
    )
    (net (code "74") (name "unconnected-(U1-SPI_MOSI{slash}GPIO{slash}EINT_d-Pad4)") (class "Default")
      (node (ref "U1") (pin "4") (pinfunction "SPI_MOSI/GPIO/EINT_d_4") (pintype "unspecified+no_connect"))
    )
    (net (code "75") (name "unconnected-(U1-SPI_SCLK{slash}GPIO{slash}EINT_d-Pad5)") (class "Default")
      (node (ref "U1") (pin "5") (pinfunction "SPI_SCLK/GPIO/EINT_d_5") (pintype "unspecified+no_connect"))
    )
    (net (code "76") (name "unconnected-(U1-TXD_AUX{slash}GPIO{slash}EINT_d-Pad29)") (class "Default")
      (node (ref "U1") (pin "29") (pinfunction "TXD_AUX/GPIO/EINT_d_29") (pintype "unspecified+no_connect"))
    )
    (net (code "77") (name "unconnected-(U1-TXD_DBG{slash}GPIO{slash}EINT_d-Pad39)") (class "Default")
      (node (ref "U1") (pin "39") (pinfunction "TXD_DBG/GPIO/EINT_d_39") (pintype "unspecified+no_connect"))
    )
    (net (code "78") (name "unconnected-(U2-3V3_EN-Pad37)") (class "Default")
      (node (ref "U2") (pin "37") (pinfunction "3V3_EN_37") (pintype "unspecified+no_connect"))
    )
    (net (code "79") (name "unconnected-(U2-ADC_VREF-Pad35)") (class "Default")
      (node (ref "U2") (pin "35") (pinfunction "ADC_VREF_35") (pintype "unspecified+no_connect"))
    )
    (net (code "80") (name "unconnected-(U2-GP6-Pad9)") (class "Default")
      (node (ref "U2") (pin "9") (pinfunction "GP6_9") (pintype "unspecified+no_connect"))
    )
    (net (code "81") (name "unconnected-(U2-GP7-Pad10)") (class "Default")
      (node (ref "U2") (pin "10") (pinfunction "GP7_10") (pintype "unspecified+no_connect"))
    )
    (net (code "82") (name "unconnected-(U2-GP8-Pad11)") (class "Default")
      (node (ref "U2") (pin "11") (pinfunction "GP8_11") (pintype "unspecified+no_connect"))
    )
    (net (code "83") (name "unconnected-(U2-GP9-Pad12)") (class "Default")
      (node (ref "U2") (pin "12") (pinfunction "GP9_12") (pintype "unspecified+no_connect"))
    )
    (net (code "84") (name "unconnected-(U2-GP10-Pad14)") (class "Default")
      (node (ref "U2") (pin "14") (pinfunction "GP10_14") (pintype "unspecified+no_connect"))
    )
    (net (code "85") (name "unconnected-(U2-GP11-Pad15)") (class "Default")
      (node (ref "U2") (pin "15") (pinfunction "GP11_15") (pintype "unspecified+no_connect"))
    )
    (net (code "86") (name "unconnected-(U2-GP12-Pad16)") (class "Default")
      (node (ref "U2") (pin "16") (pinfunction "GP12_16") (pintype "unspecified+no_connect"))
    )
    (net (code "87") (name "unconnected-(U2-GP16{slash}SPIRX-Pad21)") (class "Default")
      (node (ref "U2") (pin "21") (pinfunction "GP16/SPIRX_21") (pintype "unspecified+no_connect"))
    )
    (net (code "88") (name "unconnected-(U2-GP17{slash}SPICS-Pad22)") (class "Default")
      (node (ref "U2") (pin "22") (pinfunction "GP17/SPICS_22") (pintype "unspecified+no_connect"))
    )
    (net (code "89") (name "unconnected-(U2-GP18{slash}SPISCK-Pad24)") (class "Default")
      (node (ref "U2") (pin "24") (pinfunction "GP18/SPISCK_24") (pintype "unspecified+no_connect"))
    )
    (net (code "90") (name "unconnected-(U2-GP19{slash}SPITX-Pad25)") (class "Default")
      (node (ref "U2") (pin "25") (pinfunction "GP19/SPITX_25") (pintype "unspecified+no_connect"))
    )
    (net (code "91") (name "unconnected-(U2-GP20-Pad26)") (class "Default")
      (node (ref "U2") (pin "26") (pinfunction "GP20_26") (pintype "unspecified+no_connect"))
    )
    (net (code "92") (name "unconnected-(U2-GP21-Pad27)") (class "Default")
      (node (ref "U2") (pin "27") (pinfunction "GP21_27") (pintype "unspecified+no_connect"))
    )
    (net (code "93") (name "unconnected-(U2-GP22-Pad29)") (class "Default")
      (node (ref "U2") (pin "29") (pinfunction "GP22_29") (pintype "unspecified+no_connect"))
    )
    (net (code "94") (name "unconnected-(U2-GP26{slash}ADC0-Pad31)") (class "Default")
      (node (ref "U2") (pin "31") (pinfunction "GP26/ADC0_31") (pintype "unspecified+no_connect"))
    )
    (net (code "95") (name "unconnected-(U2-GP27{slash}ADC1-Pad32)") (class "Default")
      (node (ref "U2") (pin "32") (pinfunction "GP27/ADC1_32") (pintype "unspecified+no_connect"))
    )
    (net (code "96") (name "unconnected-(U2-GP28{slash}ADC2-Pad34)") (class "Default")
      (node (ref "U2") (pin "34") (pinfunction "GP28/ADC2_34") (pintype "unspecified+no_connect"))
    )
    (net (code "97") (name "unconnected-(U2-RUN-Pad30)") (class "Default")
      (node (ref "U2") (pin "30") (pinfunction "RUN_30") (pintype "unspecified+no_connect"))
    )
  )
)
